# Remote323Board.net
KiCad netlist of a schematic drawn in EasyEDA Pro
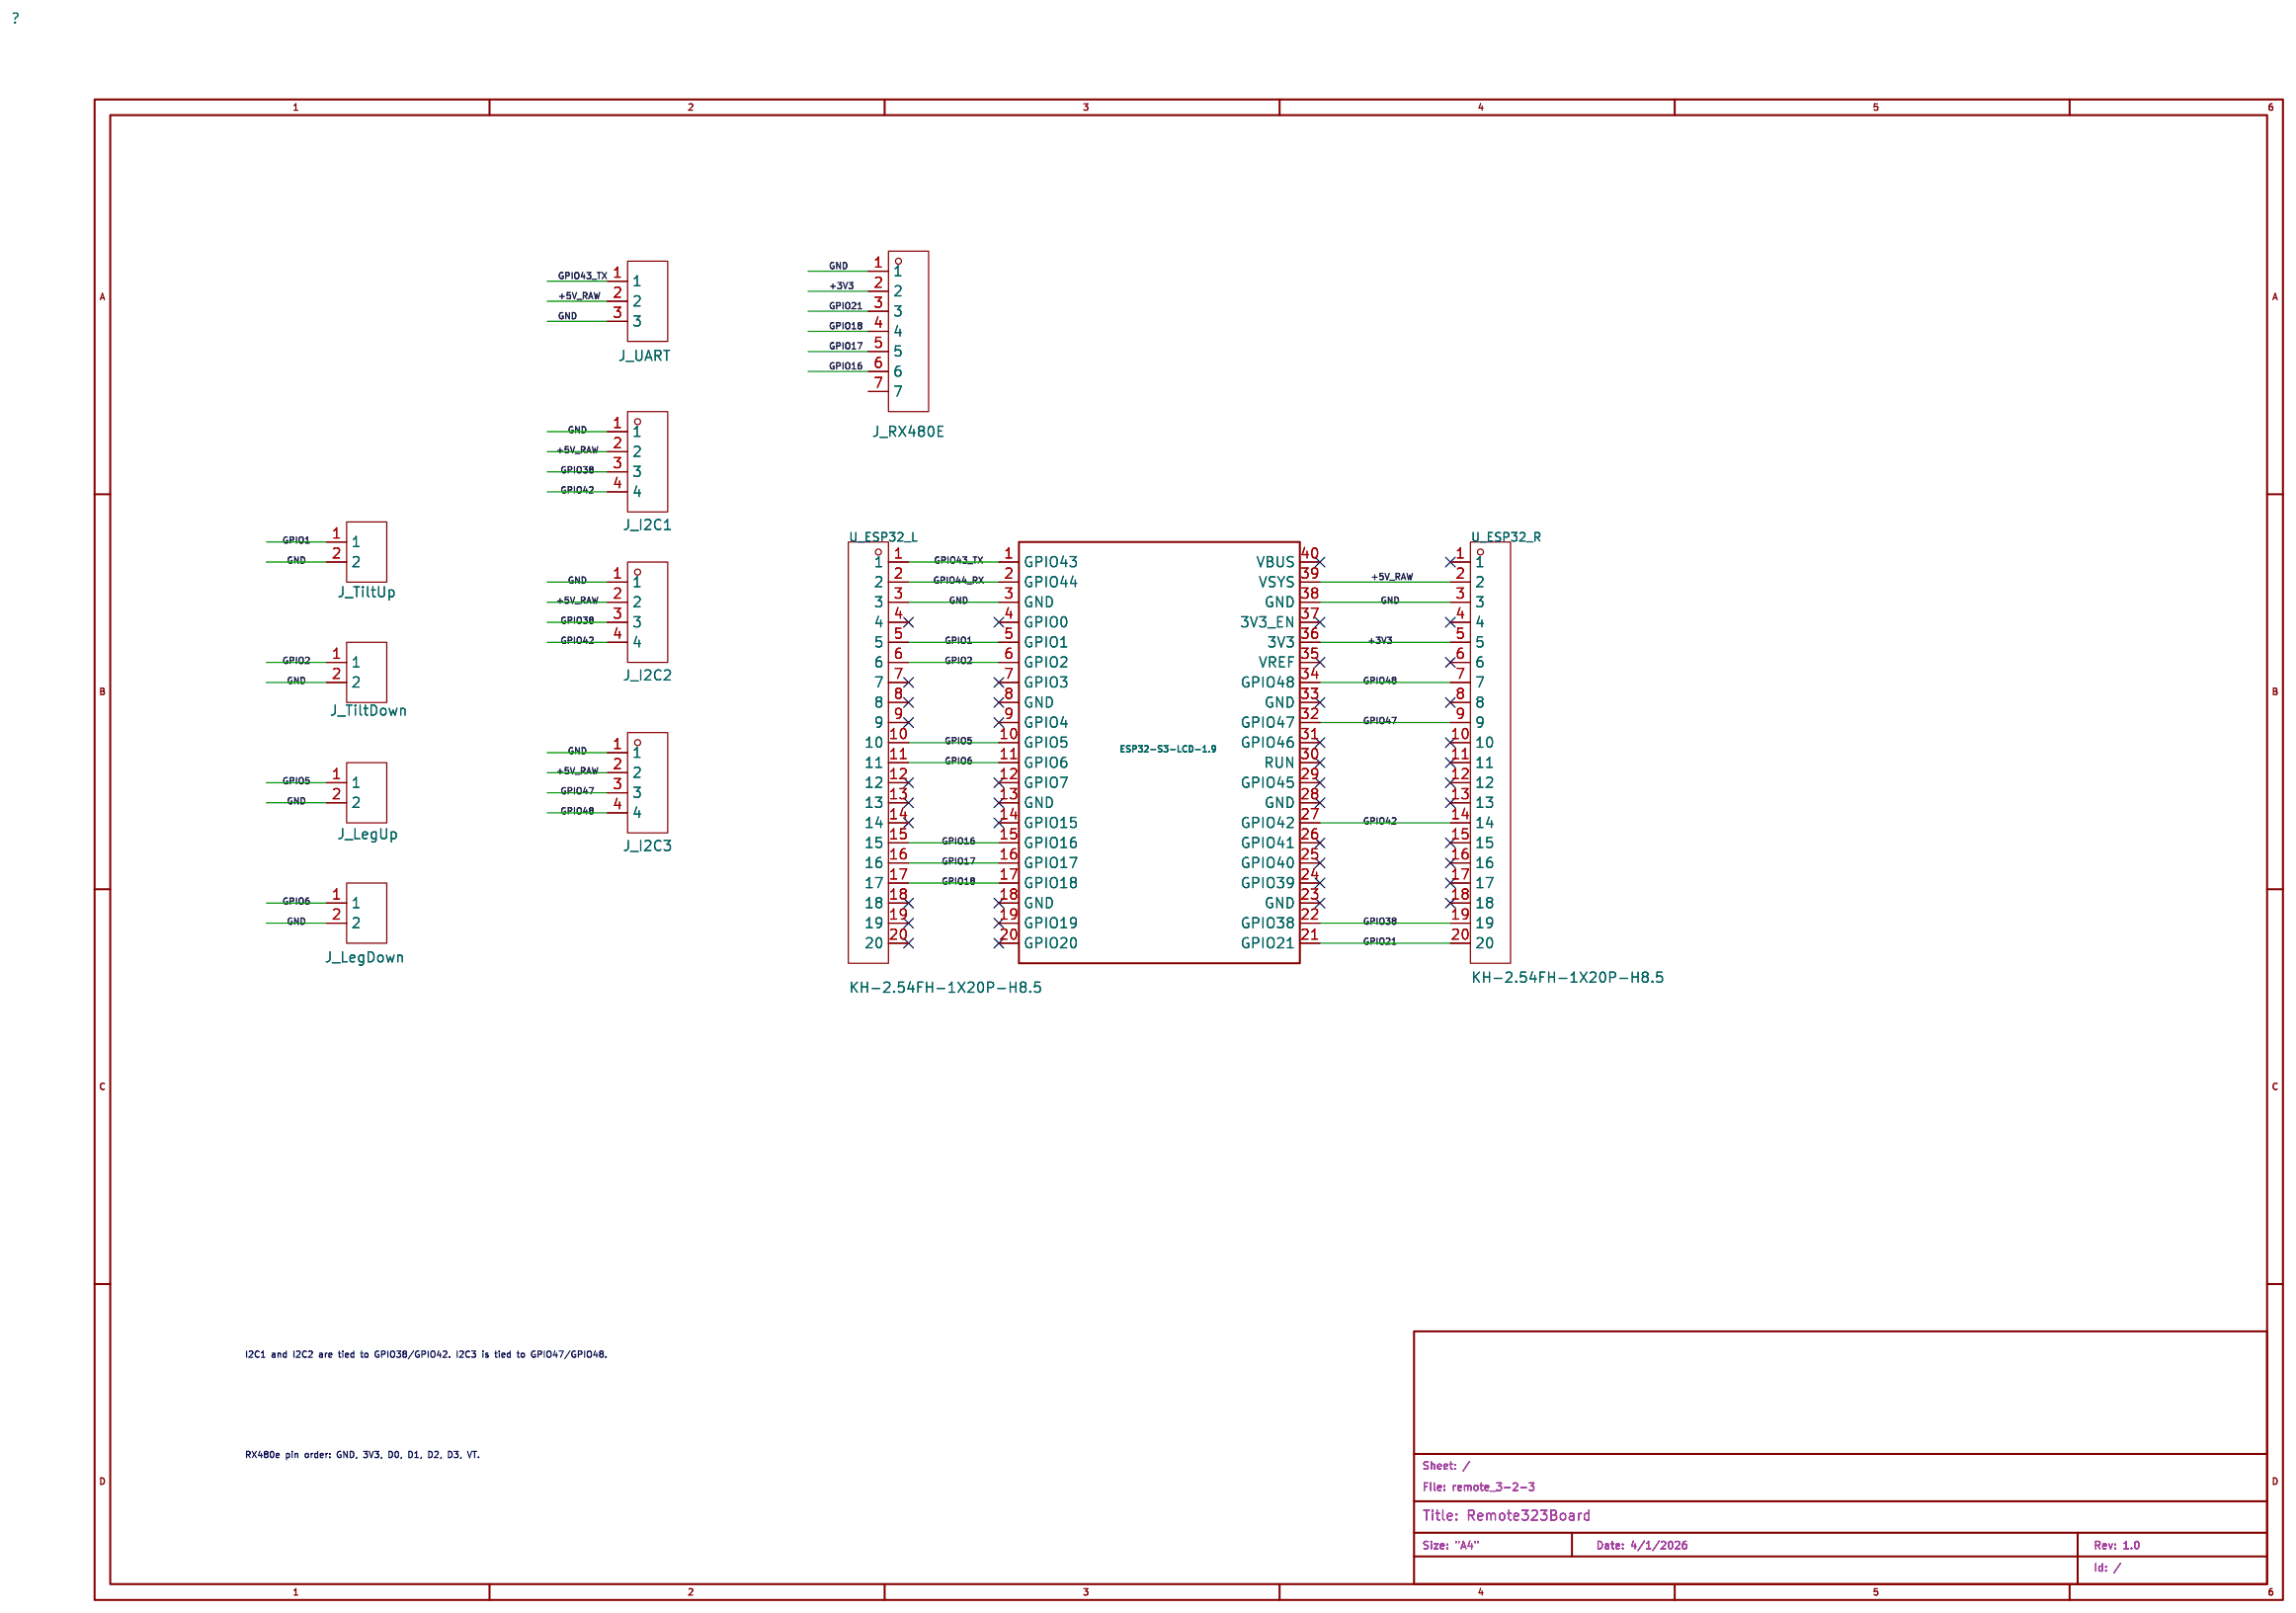
[diagram p0: schematic sheet]

(export (version "E")
  (design (tool "Eeschema 10.0.6"))
  (components
    (comp (ref "J_I2C1")
      (value "PZ254V-11-04P")
      (footprint "easyedapro:HDR-TH_4P-P2.54-V-M")
      (fields (field (name "Manufacturer") "XFCN(兴飞)"))
      (libsource (lib "easyedapro") (part "PZ254V-11-04P_C2691448"))
    )
    (comp (ref "J_I2C2")
      (value "PZ254V-11-04P")
      (footprint "easyedapro:HDR-TH_4P-P2.54-V-M")
      (fields (field (name "Manufacturer") "XFCN(兴飞)"))
      (libsource (lib "easyedapro") (part "PZ254V-11-04P_C2691448"))
    )
    (comp (ref "J_I2C3")
      (value "PZ254V-11-04P")
      (footprint "easyedapro:HDR-TH_4P-P2.54-V-M")
      (fields (field (name "Manufacturer") "XFCN(兴飞)"))
      (libsource (lib "easyedapro") (part "PZ254V-11-04P_C2691448"))
    )
    (comp (ref "J_LegDown")
      (value "PZ254V-11-02P")
      (footprint "easyedapro:HDR-TH_2P-P2.54-V-M")
      (fields (field (name "Manufacturer") "XFCN(兴飞)"))
      (libsource (lib "easyedapro") (part "PZ254V-11-02P"))
    )
    (comp (ref "J_LegUp")
      (value "PZ254V-11-02P")
      (footprint "easyedapro:HDR-TH_2P-P2.54-V-M")
      (fields (field (name "Manufacturer") "XFCN(兴飞)"))
      (libsource (lib "easyedapro") (part "PZ254V-11-02P"))
    )
    (comp (ref "J_RX480E")
      (value "HC-PM254-5.0H-1x7PZ")
      (footprint "easyedapro:HDR-TH_7P-P2.54-V-M-3")
      (fields (field (name "Manufacturer") "HC(虹成电子)"))
      (libsource (lib "easyedapro") (part "HC-PM254-5.0H-1X7PZ"))
    )
    (comp (ref "J_TiltDown")
      (value "PZ254V-11-02P")
      (footprint "easyedapro:HDR-TH_2P-P2.54-V-M")
      (fields (field (name "Manufacturer") "XFCN(兴飞)"))
      (libsource (lib "easyedapro") (part "PZ254V-11-02P"))
    )
    (comp (ref "J_TiltUp")
      (value "PZ254V-11-02P")
      (footprint "easyedapro:HDR-TH_2P-P2.54-V-M")
      (fields (field (name "Manufacturer") "XFCN(兴飞)"))
      (libsource (lib "easyedapro") (part "PZ254V-11-02P"))
    )
    (comp (ref "J_UART")
      (value "PZ254V-11-03P")
      (footprint "easyedapro:HDR-TH_3P-P2.54-V-M_PZ254V-11-03P")
      (fields (field (name "Manufacturer") "XFCN(兴飞)"))
      (libsource (lib "easyedapro") (part "PZ254V-11-03P_C2937625"))
    )
    (comp (ref "U1")
      (value "ESP32-S3-LCD-1.9")
      (libsource (lib "easyedapro") (part "Remote323_Waveshare_ESP32_S3_LCD_1_9"))
    )
    (comp (ref "U_ESP32_L")
      (value "KH-2.54FH-1X20P-H8.5")
      (footprint "easyedapro:HDR-TH_20P-P2.54-V-F-2")
      (fields (field (name "Manufacturer") "kinghelm(金航标)"))
      (libsource (lib "easyedapro") (part "KH-2.54FH-1X20P-H8.5"))
    )
    (comp (ref "U_ESP32_R")
      (value "KH-2.54FH-1X20P-H8.5")
      (footprint "easyedapro:HDR-TH_20P-P2.54-V-F-2")
      (fields (field (name "Manufacturer") "kinghelm(金航标)"))
      (libsource (lib "easyedapro") (part "KH-2.54FH-1X20P-H8.5"))
    )
  )
  (nets
    (net (code "1") (name "/+3V3") (class "Default")
      (node (ref "J_RX480E") (pin "2") (pinfunction "2_2") (pintype "unspecified"))
      (node (ref "U1") (pin "36") (pinfunction "3V3_36") (pintype "unspecified"))
      (node (ref "U_ESP32_R") (pin "5") (pinfunction "5_5") (pintype "input"))
    )
    (net (code "2") (name "/+5V_RAW") (class "Default")
      (node (ref "J_I2C1") (pin "2") (pinfunction "2_2") (pintype "input"))
      (node (ref "J_I2C2") (pin "2") (pinfunction "2_2") (pintype "input"))
      (node (ref "J_I2C3") (pin "2") (pinfunction "2_2") (pintype "input"))
      (node (ref "J_UART") (pin "2") (pinfunction "2_2") (pintype "unspecified"))
      (node (ref "U1") (pin "39") (pinfunction "VSYS_39") (pintype "unspecified"))
      (node (ref "U_ESP32_R") (pin "2") (pinfunction "2_2") (pintype "input"))
    )
    (net (code "3") (name "/GND") (class "Default")
      (node (ref "J_I2C1") (pin "1") (pinfunction "1_1") (pintype "input"))
      (node (ref "J_I2C2") (pin "1") (pinfunction "1_1") (pintype "input"))
      (node (ref "J_I2C3") (pin "1") (pinfunction "1_1") (pintype "input"))
      (node (ref "J_LegDown") (pin "2") (pinfunction "2_2") (pintype "unspecified"))
      (node (ref "J_LegUp") (pin "2") (pinfunction "2_2") (pintype "unspecified"))
      (node (ref "J_RX480E") (pin "1") (pinfunction "1_1") (pintype "unspecified"))
      (node (ref "J_TiltDown") (pin "2") (pinfunction "2_2") (pintype "unspecified"))
      (node (ref "J_TiltUp") (pin "2") (pinfunction "2_2") (pintype "unspecified"))
      (node (ref "J_UART") (pin "3") (pinfunction "3_3") (pintype "unspecified"))
      (node (ref "U1") (pin "3") (pinfunction "GND_3") (pintype "unspecified"))
      (node (ref "U1") (pin "38") (pinfunction "GND_38") (pintype "unspecified"))
      (node (ref "U_ESP32_L") (pin "3") (pinfunction "3_3") (pintype "input"))
      (node (ref "U_ESP32_R") (pin "3") (pinfunction "3_3") (pintype "input"))
    )
    (net (code "4") (name "/GPIO1") (class "Default")
      (node (ref "J_TiltUp") (pin "1") (pinfunction "1_1") (pintype "unspecified"))
      (node (ref "U1") (pin "5") (pinfunction "GPIO1_5") (pintype "unspecified"))
      (node (ref "U_ESP32_L") (pin "5") (pinfunction "5_5") (pintype "input"))
    )
    (net (code "5") (name "/GPIO2") (class "Default")
      (node (ref "J_TiltDown") (pin "1") (pinfunction "1_1") (pintype "unspecified"))
      (node (ref "U1") (pin "6") (pinfunction "GPIO2_6") (pintype "unspecified"))
      (node (ref "U_ESP32_L") (pin "6") (pinfunction "6_6") (pintype "input"))
    )
    (net (code "6") (name "/GPIO5") (class "Default")
      (node (ref "J_LegUp") (pin "1") (pinfunction "1_1") (pintype "unspecified"))
      (node (ref "U1") (pin "10") (pinfunction "GPIO5_10") (pintype "unspecified"))
      (node (ref "U_ESP32_L") (pin "10") (pinfunction "10_10") (pintype "input"))
    )
    (net (code "7") (name "/GPIO6") (class "Default")
      (node (ref "J_LegDown") (pin "1") (pinfunction "1_1") (pintype "unspecified"))
      (node (ref "U1") (pin "11") (pinfunction "GPIO6_11") (pintype "unspecified"))
      (node (ref "U_ESP32_L") (pin "11") (pinfunction "11_11") (pintype "input"))
    )
    (net (code "8") (name "/GPIO16") (class "Default")
      (node (ref "J_RX480E") (pin "6") (pinfunction "6_6") (pintype "unspecified"))
      (node (ref "U1") (pin "15") (pinfunction "GPIO16_15") (pintype "unspecified"))
      (node (ref "U_ESP32_L") (pin "15") (pinfunction "15_15") (pintype "input"))
    )
    (net (code "9") (name "/GPIO17") (class "Default")
      (node (ref "J_RX480E") (pin "5") (pinfunction "5_5") (pintype "unspecified"))
      (node (ref "U1") (pin "16") (pinfunction "GPIO17_16") (pintype "unspecified"))
      (node (ref "U_ESP32_L") (pin "16") (pinfunction "16_16") (pintype "input"))
    )
    (net (code "10") (name "/GPIO18") (class "Default")
      (node (ref "J_RX480E") (pin "4") (pinfunction "4_4") (pintype "unspecified"))
      (node (ref "U1") (pin "17") (pinfunction "GPIO18_17") (pintype "unspecified"))
      (node (ref "U_ESP32_L") (pin "17") (pinfunction "17_17") (pintype "input"))
    )
    (net (code "11") (name "/GPIO21") (class "Default")
      (node (ref "J_RX480E") (pin "3") (pinfunction "3_3") (pintype "unspecified"))
      (node (ref "U1") (pin "21") (pinfunction "GPIO21_21") (pintype "unspecified"))
      (node (ref "U_ESP32_R") (pin "20") (pinfunction "20_20") (pintype "input"))
    )
    (net (code "12") (name "/GPIO38") (class "Default")
      (node (ref "J_I2C1") (pin "3") (pinfunction "3_3") (pintype "input"))
      (node (ref "J_I2C2") (pin "3") (pinfunction "3_3") (pintype "input"))
      (node (ref "U1") (pin "22") (pinfunction "GPIO38_22") (pintype "unspecified"))
      (node (ref "U_ESP32_R") (pin "19") (pinfunction "19_19") (pintype "input"))
    )
    (net (code "13") (name "/GPIO42") (class "Default")
      (node (ref "J_I2C1") (pin "4") (pinfunction "4_4") (pintype "input"))
      (node (ref "J_I2C2") (pin "4") (pinfunction "4_4") (pintype "input"))
      (node (ref "U1") (pin "27") (pinfunction "GPIO42_27") (pintype "unspecified"))
      (node (ref "U_ESP32_R") (pin "14") (pinfunction "14_14") (pintype "input"))
    )
    (net (code "14") (name "/GPIO43_TX") (class "Default")
      (node (ref "J_UART") (pin "1") (pinfunction "1_1") (pintype "unspecified"))
      (node (ref "U1") (pin "1") (pinfunction "GPIO43_1") (pintype "unspecified"))
      (node (ref "U_ESP32_L") (pin "1") (pinfunction "1_1") (pintype "input"))
    )
    (net (code "15") (name "/GPIO44_RX") (class "Default")
      (node (ref "U1") (pin "2") (pinfunction "GPIO44_2") (pintype "unspecified"))
      (node (ref "U_ESP32_L") (pin "2") (pinfunction "2_2") (pintype "input"))
    )
    (net (code "16") (name "/GPIO47") (class "Default")
      (node (ref "J_I2C3") (pin "3") (pinfunction "3_3") (pintype "input"))
      (node (ref "U1") (pin "32") (pinfunction "GPIO47_32") (pintype "unspecified"))
      (node (ref "U_ESP32_R") (pin "9") (pinfunction "9_9") (pintype "input"))
    )
    (net (code "17") (name "/GPIO48") (class "Default")
      (node (ref "J_I2C3") (pin "4") (pinfunction "4_4") (pintype "input"))
      (node (ref "U1") (pin "34") (pinfunction "GPIO48_34") (pintype "unspecified"))
      (node (ref "U_ESP32_R") (pin "7") (pinfunction "7_7") (pintype "input"))
    )
    (net (code "18") (name "unconnected-(J_RX480E-Pad7)") (class "Default")
      (node (ref "J_RX480E") (pin "7") (pinfunction "7_7") (pintype "unspecified"))
    )
    (net (code "19") (name "unconnected-(U1-3V3_EN-Pad37)") (class "Default")
      (node (ref "U1") (pin "37") (pinfunction "3V3_EN_37") (pintype "unspecified+no_connect"))
    )
    (net (code "20") (name "unconnected-(U1-GND-Pad8)") (class "Default")
      (node (ref "U1") (pin "8") (pinfunction "GND_8") (pintype "unspecified+no_connect"))
    )
    (net (code "21") (name "unconnected-(U1-GND-Pad13)") (class "Default")
      (node (ref "U1") (pin "13") (pinfunction "GND_13") (pintype "unspecified+no_connect"))
    )
    (net (code "22") (name "unconnected-(U1-GND-Pad18)") (class "Default")
      (node (ref "U1") (pin "18") (pinfunction "GND_18") (pintype "unspecified+no_connect"))
    )
    (net (code "23") (name "unconnected-(U1-GND-Pad23)") (class "Default")
      (node (ref "U1") (pin "23") (pinfunction "GND_23") (pintype "unspecified+no_connect"))
    )
    (net (code "24") (name "unconnected-(U1-GND-Pad28)") (class "Default")
      (node (ref "U1") (pin "28") (pinfunction "GND_28") (pintype "unspecified+no_connect"))
    )
    (net (code "25") (name "unconnected-(U1-GND-Pad33)") (class "Default")
      (node (ref "U1") (pin "33") (pinfunction "GND_33") (pintype "unspecified+no_connect"))
    )
    (net (code "26") (name "unconnected-(U1-GPIO0-Pad4)") (class "Default")
      (node (ref "U1") (pin "4") (pinfunction "GPIO0_4") (pintype "unspecified+no_connect"))
    )
    (net (code "27") (name "unconnected-(U1-GPIO3-Pad7)") (class "Default")
      (node (ref "U1") (pin "7") (pinfunction "GPIO3_7") (pintype "unspecified+no_connect"))
    )
    (net (code "28") (name "unconnected-(U1-GPIO4-Pad9)") (class "Default")
      (node (ref "U1") (pin "9") (pinfunction "GPIO4_9") (pintype "unspecified+no_connect"))
    )
    (net (code "29") (name "unconnected-(U1-GPIO7-Pad12)") (class "Default")
      (node (ref "U1") (pin "12") (pinfunction "GPIO7_12") (pintype "unspecified+no_connect"))
    )
    (net (code "30") (name "unconnected-(U1-GPIO15-Pad14)") (class "Default")
      (node (ref "U1") (pin "14") (pinfunction "GPIO15_14") (pintype "unspecified+no_connect"))
    )
    (net (code "31") (name "unconnected-(U1-GPIO19-Pad19)") (class "Default")
      (node (ref "U1") (pin "19") (pinfunction "GPIO19_19") (pintype "unspecified+no_connect"))
    )
    (net (code "32") (name "unconnected-(U1-GPIO20-Pad20)") (class "Default")
      (node (ref "U1") (pin "20") (pinfunction "GPIO20_20") (pintype "unspecified+no_connect"))
    )
    (net (code "33") (name "unconnected-(U1-GPIO39-Pad24)") (class "Default")
      (node (ref "U1") (pin "24") (pinfunction "GPIO39_24") (pintype "unspecified+no_connect"))
    )
    (net (code "34") (name "unconnected-(U1-GPIO40-Pad25)") (class "Default")
      (node (ref "U1") (pin "25") (pinfunction "GPIO40_25") (pintype "unspecified+no_connect"))
    )
    (net (code "35") (name "unconnected-(U1-GPIO41-Pad26)") (class "Default")
      (node (ref "U1") (pin "26") (pinfunction "GPIO41_26") (pintype "unspecified+no_connect"))
    )
    (net (code "36") (name "unconnected-(U1-GPIO45-Pad29)") (class "Default")
      (node (ref "U1") (pin "29") (pinfunction "GPIO45_29") (pintype "unspecified+no_connect"))
    )
    (net (code "37") (name "unconnected-(U1-GPIO46-Pad31)") (class "Default")
      (node (ref "U1") (pin "31") (pinfunction "GPIO46_31") (pintype "unspecified+no_connect"))
    )
    (net (code "38") (name "unconnected-(U1-RUN-Pad30)") (class "Default")
      (node (ref "U1") (pin "30") (pinfunction "RUN_30") (pintype "unspecified+no_connect"))
    )
    (net (code "39") (name "unconnected-(U1-VBUS-Pad40)") (class "Default")
      (node (ref "U1") (pin "40") (pinfunction "VBUS_40") (pintype "unspecified+no_connect"))
    )
    (net (code "40") (name "unconnected-(U1-VREF-Pad35)") (class "Default")
      (node (ref "U1") (pin "35") (pinfunction "VREF_35") (pintype "unspecified+no_connect"))
    )
    (net (code "41") (name "unconnected-(U_ESP32_L-Pad4)") (class "Default")
      (node (ref "U_ESP32_L") (pin "4") (pinfunction "4_4") (pintype "input+no_connect"))
    )
    (net (code "42") (name "unconnected-(U_ESP32_L-Pad7)") (class "Default")
      (node (ref "U_ESP32_L") (pin "7") (pinfunction "7_7") (pintype "input+no_connect"))
    )
    (net (code "43") (name "unconnected-(U_ESP32_L-Pad8)") (class "Default")
      (node (ref "U_ESP32_L") (pin "8") (pinfunction "8_8") (pintype "input+no_connect"))
    )
    (net (code "44") (name "unconnected-(U_ESP32_L-Pad9)") (class "Default")
      (node (ref "U_ESP32_L") (pin "9") (pinfunction "9_9") (pintype "input+no_connect"))
    )
    (net (code "45") (name "unconnected-(U_ESP32_L-Pad12)") (class "Default")
      (node (ref "U_ESP32_L") (pin "12") (pinfunction "12_12") (pintype "input+no_connect"))
    )
    (net (code "46") (name "unconnected-(U_ESP32_L-Pad13)") (class "Default")
      (node (ref "U_ESP32_L") (pin "13") (pinfunction "13_13") (pintype "input+no_connect"))
    )
    (net (code "47") (name "unconnected-(U_ESP32_L-Pad14)") (class "Default")
      (node (ref "U_ESP32_L") (pin "14") (pinfunction "14_14") (pintype "input+no_connect"))
    )
    (net (code "48") (name "unconnected-(U_ESP32_L-Pad18)") (class "Default")
      (node (ref "U_ESP32_L") (pin "18") (pinfunction "18_18") (pintype "input+no_connect"))
    )
    (net (code "49") (name "unconnected-(U_ESP32_L-Pad19)") (class "Default")
      (node (ref "U_ESP32_L") (pin "19") (pinfunction "19_19") (pintype "input+no_connect"))
    )
    (net (code "50") (name "unconnected-(U_ESP32_L-Pad20)") (class "Default")
      (node (ref "U_ESP32_L") (pin "20") (pinfunction "20_20") (pintype "input+no_connect"))
    )
    (net (code "51") (name "unconnected-(U_ESP32_R-Pad1)") (class "Default")
      (node (ref "U_ESP32_R") (pin "1") (pinfunction "1_1") (pintype "input+no_connect"))
    )
    (net (code "52") (name "unconnected-(U_ESP32_R-Pad4)") (class "Default")
      (node (ref "U_ESP32_R") (pin "4") (pinfunction "4_4") (pintype "input+no_connect"))
    )
    (net (code "53") (name "unconnected-(U_ESP32_R-Pad6)") (class "Default")
      (node (ref "U_ESP32_R") (pin "6") (pinfunction "6_6") (pintype "input+no_connect"))
    )
    (net (code "54") (name "unconnected-(U_ESP32_R-Pad8)") (class "Default")
      (node (ref "U_ESP32_R") (pin "8") (pinfunction "8_8") (pintype "input+no_connect"))
    )
    (net (code "55") (name "unconnected-(U_ESP32_R-Pad10)") (class "Default")
      (node (ref "U_ESP32_R") (pin "10") (pinfunction "10_10") (pintype "input+no_connect"))
    )
    (net (code "56") (name "unconnected-(U_ESP32_R-Pad11)") (class "Default")
      (node (ref "U_ESP32_R") (pin "11") (pinfunction "11_11") (pintype "input+no_connect"))
    )
    (net (code "57") (name "unconnected-(U_ESP32_R-Pad12)") (class "Default")
      (node (ref "U_ESP32_R") (pin "12") (pinfunction "12_12") (pintype "input+no_connect"))
    )
    (net (code "58") (name "unconnected-(U_ESP32_R-Pad13)") (class "Default")
      (node (ref "U_ESP32_R") (pin "13") (pinfunction "13_13") (pintype "input+no_connect"))
    )
    (net (code "59") (name "unconnected-(U_ESP32_R-Pad15)") (class "Default")
      (node (ref "U_ESP32_R") (pin "15") (pinfunction "15_15") (pintype "input+no_connect"))
    )
    (net (code "60") (name "unconnected-(U_ESP32_R-Pad16)") (class "Default")
      (node (ref "U_ESP32_R") (pin "16") (pinfunction "16_16") (pintype "input+no_connect"))
    )
    (net (code "61") (name "unconnected-(U_ESP32_R-Pad17)") (class "Default")
      (node (ref "U_ESP32_R") (pin "17") (pinfunction "17_17") (pintype "input+no_connect"))
    )
    (net (code "62") (name "unconnected-(U_ESP32_R-Pad18)") (class "Default")
      (node (ref "U_ESP32_R") (pin "18") (pinfunction "18_18") (pintype "input+no_connect"))
    )
  )
)
